# LB_o9_Bargraph-v03_3_3.net
KiCad netlist of a schematic drawn in EAGLE
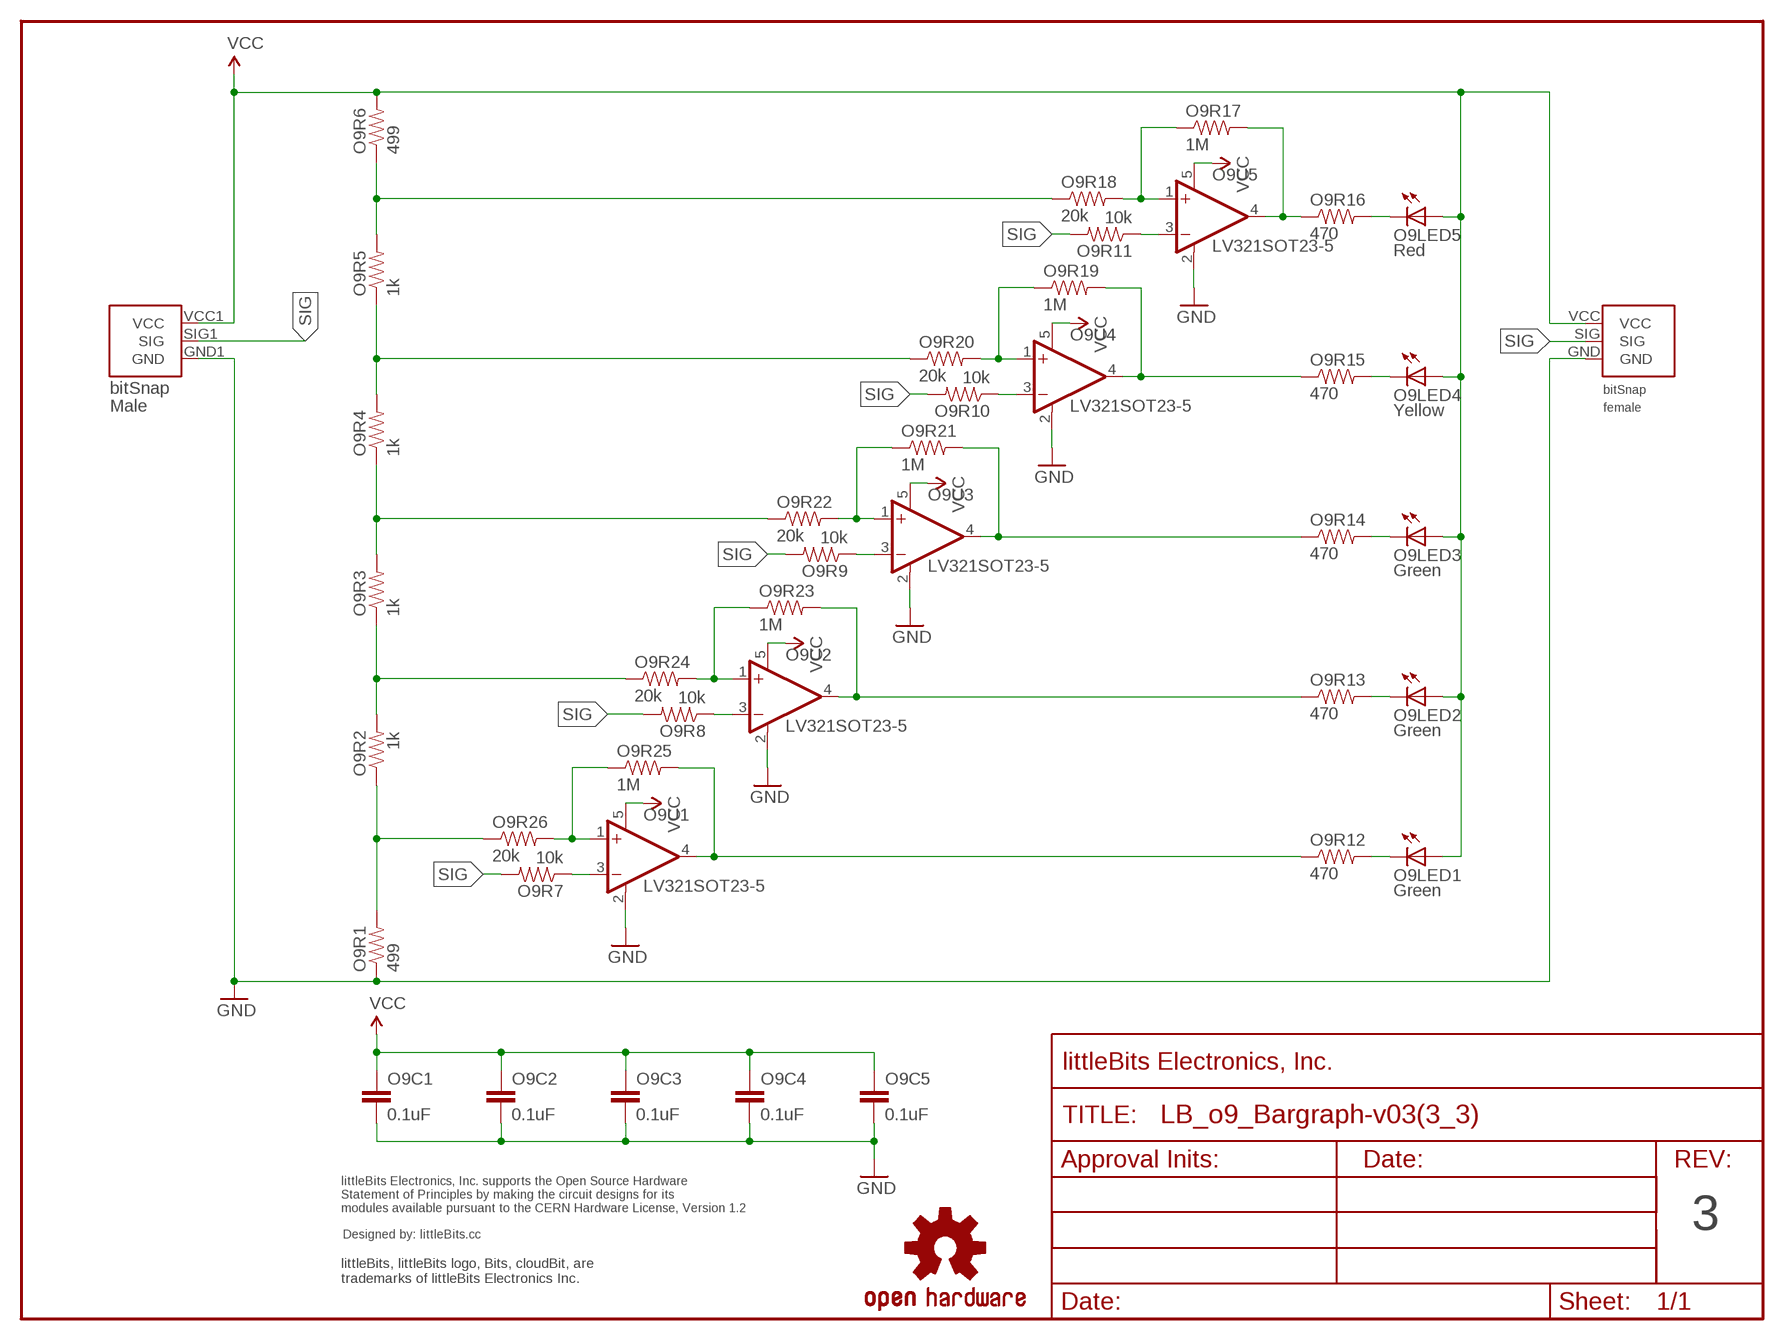
[diagram p0: schematic, sheet 1]

(export (version "E")
  (design (tool "Eeschema 10.0.6"))
  (components
    (comp (ref "09BSF1")
      (value "BITSNAP_V03_FEMALE")
      (footprint "eagle-import:BITSNAP_V03_FEMALE")
      (libsource (lib "eagle-import") (part "BITSNAP_V03_FEMALE"))
    )
    (comp (ref "O9BSM1")
      (value "BITSNAP_V03_MALE")
      (footprint "eagle-import:BITSNAP_V03_MALE")
      (libsource (lib "eagle-import") (part "BITSNAP_V03_MALE"))
    )
    (comp (ref "O9C1")
      (value "0.1uF")
      (footprint "eagle-import:0603-CAP")
      (libsource (lib "eagle-import") (part "CAP0603-CAP"))
    )
    (comp (ref "O9C2")
      (value "0.1uF")
      (footprint "eagle-import:0603-CAP")
      (libsource (lib "eagle-import") (part "CAP0603-CAP"))
    )
    (comp (ref "O9C3")
      (value "0.1uF")
      (footprint "eagle-import:0603-CAP")
      (libsource (lib "eagle-import") (part "CAP0603-CAP"))
    )
    (comp (ref "O9C4")
      (value "0.1uF")
      (footprint "eagle-import:0603-CAP")
      (libsource (lib "eagle-import") (part "CAP0603-CAP"))
    )
    (comp (ref "O9C5")
      (value "0.1uF")
      (footprint "eagle-import:0603-CAP")
      (libsource (lib "eagle-import") (part "CAP0603-CAP"))
    )
    (comp (ref "O9LED1")
      (value "Green")
      (footprint "eagle-import:LED-1206")
      (libsource (lib "eagle-import") (part "LED1206"))
    )
    (comp (ref "O9LED2")
      (value "Green")
      (footprint "eagle-import:LED-1206")
      (libsource (lib "eagle-import") (part "LED1206"))
    )
    (comp (ref "O9LED3")
      (value "Green")
      (footprint "eagle-import:LED-1206")
      (libsource (lib "eagle-import") (part "LED1206"))
    )
    (comp (ref "O9LED4")
      (value "Yellow")
      (footprint "eagle-import:LED-1206")
      (libsource (lib "eagle-import") (part "LED1206"))
    )
    (comp (ref "O9LED5")
      (value "Red")
      (footprint "eagle-import:LED-1206")
      (libsource (lib "eagle-import") (part "LED1206"))
    )
    (comp (ref "O9R1")
      (value "499")
      (footprint "eagle-import:0603-RES")
      (libsource (lib "eagle-import") (part "RESISTOR0603-RES"))
    )
    (comp (ref "O9R2")
      (value "1k")
      (footprint "eagle-import:0603-RES")
      (libsource (lib "eagle-import") (part "RESISTOR0603-RES"))
    )
    (comp (ref "O9R3")
      (value "1k")
      (footprint "eagle-import:0603-RES")
      (libsource (lib "eagle-import") (part "RESISTOR0603-RES"))
    )
    (comp (ref "O9R4")
      (value "1k")
      (footprint "eagle-import:0603-RES")
      (libsource (lib "eagle-import") (part "RESISTOR0603-RES"))
    )
    (comp (ref "O9R5")
      (value "1k")
      (footprint "eagle-import:0603-RES")
      (libsource (lib "eagle-import") (part "RESISTOR0603-RES"))
    )
    (comp (ref "O9R6")
      (value "499")
      (footprint "eagle-import:0603-RES")
      (libsource (lib "eagle-import") (part "RESISTOR0603-RES"))
    )
    (comp (ref "O9R7")
      (value "10k")
      (footprint "eagle-import:0603-RES")
      (libsource (lib "eagle-import") (part "RESISTOR0603-RES"))
    )
    (comp (ref "O9R8")
      (value "10k")
      (footprint "eagle-import:0603-RES")
      (libsource (lib "eagle-import") (part "RESISTOR0603-RES"))
    )
    (comp (ref "O9R9")
      (value "10k")
      (footprint "eagle-import:0603-RES")
      (libsource (lib "eagle-import") (part "RESISTOR0603-RES"))
    )
    (comp (ref "O9R10")
      (value "10k")
      (footprint "eagle-import:0603-RES")
      (libsource (lib "eagle-import") (part "RESISTOR0603-RES"))
    )
    (comp (ref "O9R11")
      (value "10k")
      (footprint "eagle-import:0603-RES")
      (libsource (lib "eagle-import") (part "RESISTOR0603-RES"))
    )
    (comp (ref "O9R12")
      (value "470")
      (footprint "eagle-import:0603-RES")
      (libsource (lib "eagle-import") (part "RESISTOR0603-RES"))
    )
    (comp (ref "O9R13")
      (value "470")
      (footprint "eagle-import:0603-RES")
      (libsource (lib "eagle-import") (part "RESISTOR0603-RES"))
    )
    (comp (ref "O9R14")
      (value "470")
      (footprint "eagle-import:0603-RES")
      (libsource (lib "eagle-import") (part "RESISTOR0603-RES"))
    )
    (comp (ref "O9R15")
      (value "470")
      (footprint "eagle-import:0603-RES")
      (libsource (lib "eagle-import") (part "RESISTOR0603-RES"))
    )
    (comp (ref "O9R16")
      (value "470")
      (footprint "eagle-import:0603-RES")
      (libsource (lib "eagle-import") (part "RESISTOR0603-RES"))
    )
    (comp (ref "O9R17")
      (value "1M")
      (footprint "eagle-import:0603-RES")
      (libsource (lib "eagle-import") (part "RESISTOR0603-RES"))
    )
    (comp (ref "O9R18")
      (value "20k")
      (footprint "eagle-import:0603-RES")
      (libsource (lib "eagle-import") (part "RESISTOR0603-RES"))
    )
    (comp (ref "O9R19")
      (value "1M")
      (footprint "eagle-import:0603-RES")
      (libsource (lib "eagle-import") (part "RESISTOR0603-RES"))
    )
    (comp (ref "O9R20")
      (value "20k")
      (footprint "eagle-import:0603-RES")
      (libsource (lib "eagle-import") (part "RESISTOR0603-RES"))
    )
    (comp (ref "O9R21")
      (value "1M")
      (footprint "eagle-import:0603-RES")
      (libsource (lib "eagle-import") (part "RESISTOR0603-RES"))
    )
    (comp (ref "O9R22")
      (value "20k")
      (footprint "eagle-import:0603-RES")
      (libsource (lib "eagle-import") (part "RESISTOR0603-RES"))
    )
    (comp (ref "O9R23")
      (value "1M")
      (footprint "eagle-import:0603-RES")
      (libsource (lib "eagle-import") (part "RESISTOR0603-RES"))
    )
    (comp (ref "O9R24")
      (value "20k")
      (footprint "eagle-import:0603-RES")
      (libsource (lib "eagle-import") (part "RESISTOR0603-RES"))
    )
    (comp (ref "O9R25")
      (value "1M")
      (footprint "eagle-import:0603-RES")
      (libsource (lib "eagle-import") (part "RESISTOR0603-RES"))
    )
    (comp (ref "O9R26")
      (value "20k")
      (footprint "eagle-import:0603-RES")
      (libsource (lib "eagle-import") (part "RESISTOR0603-RES"))
    )
    (comp (ref "O9U1")
      (value "LV321SOT23-5")
      (footprint "eagle-import:SOT23-5")
      (libsource (lib "eagle-import") (part "LV321SOT23-5"))
    )
    (comp (ref "O9U2")
      (value "LV321SOT23-5")
      (footprint "eagle-import:SOT23-5")
      (libsource (lib "eagle-import") (part "LV321SOT23-5"))
    )
    (comp (ref "O9U3")
      (value "LV321SOT23-5")
      (footprint "eagle-import:SOT23-5")
      (libsource (lib "eagle-import") (part "LV321SOT23-5"))
    )
    (comp (ref "O9U4")
      (value "LV321SOT23-5")
      (footprint "eagle-import:SOT23-5")
      (libsource (lib "eagle-import") (part "LV321SOT23-5"))
    )
    (comp (ref "O9U5")
      (value "LV321SOT23-5")
      (footprint "eagle-import:SOT23-5")
      (libsource (lib "eagle-import") (part "LV321SOT23-5"))
    )
    (comp (ref "U$1")
      (value "OSHWCREDIT")
      (footprint "eagle-import:OSHWCREDIT")
      (libsource (lib "eagle-import") (part "OSHWCREDIT"))
    )
    (comp (ref "U$2")
      (value "FRAME-LETTER-OHWOHW")
      (footprint "eagle-import:FABDWG01-OHW")
      (libsource (lib "eagle-import") (part "FRAME-LETTER-OHWOHW"))
    )
    (comp (ref "U$4")
      (value "OSHW-LOGOL")
      (footprint "eagle-import:OSHW-LOGO-L")
      (libsource (lib "eagle-import") (part "OSHW-LOGOL"))
    )
  )
  (nets
    (net (code "1") (name "GND") (class "Default")
      (node (ref "09BSF1") (pin "GND") (pinfunction "GND_GND") (pintype "bidirectional"))
      (node (ref "O9BSM1") (pin "GND1") (pinfunction "GND_GND1") (pintype "bidirectional"))
      (node (ref "O9C1") (pin "2") (pinfunction "2_2") (pintype "passive"))
      (node (ref "O9C2") (pin "2") (pinfunction "2_2") (pintype "passive"))
      (node (ref "O9C3") (pin "2") (pinfunction "2_2") (pintype "passive"))
      (node (ref "O9C4") (pin "2") (pinfunction "2_2") (pintype "passive"))
      (node (ref "O9C5") (pin "2") (pinfunction "2_2") (pintype "passive"))
      (node (ref "O9R1") (pin "1") (pinfunction "1_1") (pintype "passive"))
      (node (ref "O9U1") (pin "2") (pinfunction "V-_2") (pintype "power_in"))
      (node (ref "O9U2") (pin "2") (pinfunction "V-_2") (pintype "power_in"))
      (node (ref "O9U3") (pin "2") (pinfunction "V-_2") (pintype "power_in"))
      (node (ref "O9U4") (pin "2") (pinfunction "V-_2") (pintype "power_in"))
      (node (ref "O9U5") (pin "2") (pinfunction "V-_2") (pintype "power_in"))
    )
    (net (code "2") (name "Net-(O9LED1-PadC)") (class "Default")
      (node (ref "O9LED1") (pin "C") (pinfunction "C_C") (pintype "passive"))
      (node (ref "O9R12") (pin "2") (pinfunction "2_2") (pintype "passive"))
    )
    (net (code "3") (name "Net-(O9LED2-PadC)") (class "Default")
      (node (ref "O9LED2") (pin "C") (pinfunction "C_C") (pintype "passive"))
      (node (ref "O9R13") (pin "2") (pinfunction "2_2") (pintype "passive"))
    )
    (net (code "4") (name "Net-(O9LED3-PadC)") (class "Default")
      (node (ref "O9LED3") (pin "C") (pinfunction "C_C") (pintype "passive"))
      (node (ref "O9R14") (pin "2") (pinfunction "2_2") (pintype "passive"))
    )
    (net (code "5") (name "Net-(O9LED4-PadC)") (class "Default")
      (node (ref "O9LED4") (pin "C") (pinfunction "C_C") (pintype "passive"))
      (node (ref "O9R15") (pin "2") (pinfunction "2_2") (pintype "passive"))
    )
    (net (code "6") (name "Net-(O9LED5-PadC)") (class "Default")
      (node (ref "O9LED5") (pin "C") (pinfunction "C_C") (pintype "passive"))
      (node (ref "O9R16") (pin "2") (pinfunction "2_2") (pintype "passive"))
    )
    (net (code "7") (name "Net-(O9R1-Pad2)") (class "Default")
      (node (ref "O9R1") (pin "2") (pinfunction "2_2") (pintype "passive"))
      (node (ref "O9R2") (pin "1") (pinfunction "1_1") (pintype "passive"))
      (node (ref "O9R26") (pin "1") (pinfunction "1_1") (pintype "passive"))
    )
    (net (code "8") (name "Net-(O9R2-Pad2)") (class "Default")
      (node (ref "O9R2") (pin "2") (pinfunction "2_2") (pintype "passive"))
      (node (ref "O9R24") (pin "1") (pinfunction "1_1") (pintype "passive"))
      (node (ref "O9R3") (pin "1") (pinfunction "1_1") (pintype "passive"))
    )
    (net (code "9") (name "Net-(O9R18-Pad1)") (class "Default")
      (node (ref "O9R18") (pin "1") (pinfunction "1_1") (pintype "passive"))
      (node (ref "O9R5") (pin "2") (pinfunction "2_2") (pintype "passive"))
      (node (ref "O9R6") (pin "1") (pinfunction "1_1") (pintype "passive"))
    )
    (net (code "10") (name "Net-(O9R20-Pad1)") (class "Default")
      (node (ref "O9R20") (pin "1") (pinfunction "1_1") (pintype "passive"))
      (node (ref "O9R4") (pin "2") (pinfunction "2_2") (pintype "passive"))
      (node (ref "O9R5") (pin "1") (pinfunction "1_1") (pintype "passive"))
    )
    (net (code "11") (name "Net-(O9R22-Pad1)") (class "Default")
      (node (ref "O9R22") (pin "1") (pinfunction "1_1") (pintype "passive"))
      (node (ref "O9R3") (pin "2") (pinfunction "2_2") (pintype "passive"))
      (node (ref "O9R4") (pin "1") (pinfunction "1_1") (pintype "passive"))
    )
    (net (code "12") (name "Net-(O9U1-+IN)") (class "Default")
      (node (ref "O9R25") (pin "1") (pinfunction "1_1") (pintype "passive"))
      (node (ref "O9R26") (pin "2") (pinfunction "2_2") (pintype "passive"))
      (node (ref "O9U1") (pin "1") (pinfunction "+IN_1") (pintype "input"))
    )
    (net (code "13") (name "Net-(O9U1--IN)") (class "Default")
      (node (ref "O9R7") (pin "1") (pinfunction "1_1") (pintype "passive"))
      (node (ref "O9U1") (pin "3") (pinfunction "-IN_3") (pintype "input"))
    )
    (net (code "14") (name "Net-(O9U1-OUT)") (class "Default")
      (node (ref "O9R12") (pin "1") (pinfunction "1_1") (pintype "passive"))
      (node (ref "O9R25") (pin "2") (pinfunction "2_2") (pintype "passive"))
      (node (ref "O9U1") (pin "4") (pinfunction "OUT_4") (pintype "output"))
    )
    (net (code "15") (name "Net-(O9U2-+IN)") (class "Default")
      (node (ref "O9R23") (pin "1") (pinfunction "1_1") (pintype "passive"))
      (node (ref "O9R24") (pin "2") (pinfunction "2_2") (pintype "passive"))
      (node (ref "O9U2") (pin "1") (pinfunction "+IN_1") (pintype "input"))
    )
    (net (code "16") (name "Net-(O9U2--IN)") (class "Default")
      (node (ref "O9R8") (pin "1") (pinfunction "1_1") (pintype "passive"))
      (node (ref "O9U2") (pin "3") (pinfunction "-IN_3") (pintype "input"))
    )
    (net (code "17") (name "Net-(O9U2-OUT)") (class "Default")
      (node (ref "O9R13") (pin "1") (pinfunction "1_1") (pintype "passive"))
      (node (ref "O9R23") (pin "2") (pinfunction "2_2") (pintype "passive"))
      (node (ref "O9U2") (pin "4") (pinfunction "OUT_4") (pintype "output"))
    )
    (net (code "18") (name "Net-(O9U3-+IN)") (class "Default")
      (node (ref "O9R21") (pin "1") (pinfunction "1_1") (pintype "passive"))
      (node (ref "O9R22") (pin "2") (pinfunction "2_2") (pintype "passive"))
      (node (ref "O9U3") (pin "1") (pinfunction "+IN_1") (pintype "input"))
    )
    (net (code "19") (name "Net-(O9U3--IN)") (class "Default")
      (node (ref "O9R9") (pin "1") (pinfunction "1_1") (pintype "passive"))
      (node (ref "O9U3") (pin "3") (pinfunction "-IN_3") (pintype "input"))
    )
    (net (code "20") (name "Net-(O9U3-OUT)") (class "Default")
      (node (ref "O9R14") (pin "1") (pinfunction "1_1") (pintype "passive"))
      (node (ref "O9R21") (pin "2") (pinfunction "2_2") (pintype "passive"))
      (node (ref "O9U3") (pin "4") (pinfunction "OUT_4") (pintype "output"))
    )
    (net (code "21") (name "Net-(O9U4-+IN)") (class "Default")
      (node (ref "O9R19") (pin "1") (pinfunction "1_1") (pintype "passive"))
      (node (ref "O9R20") (pin "2") (pinfunction "2_2") (pintype "passive"))
      (node (ref "O9U4") (pin "1") (pinfunction "+IN_1") (pintype "input"))
    )
    (net (code "22") (name "Net-(O9U4--IN)") (class "Default")
      (node (ref "O9R10") (pin "1") (pinfunction "1_1") (pintype "passive"))
      (node (ref "O9U4") (pin "3") (pinfunction "-IN_3") (pintype "input"))
    )
    (net (code "23") (name "Net-(O9U4-OUT)") (class "Default")
      (node (ref "O9R15") (pin "1") (pinfunction "1_1") (pintype "passive"))
      (node (ref "O9R19") (pin "2") (pinfunction "2_2") (pintype "passive"))
      (node (ref "O9U4") (pin "4") (pinfunction "OUT_4") (pintype "output"))
    )
    (net (code "24") (name "Net-(O9U5-+IN)") (class "Default")
      (node (ref "O9R17") (pin "1") (pinfunction "1_1") (pintype "passive"))
      (node (ref "O9R18") (pin "2") (pinfunction "2_2") (pintype "passive"))
      (node (ref "O9U5") (pin "1") (pinfunction "+IN_1") (pintype "input"))
    )
    (net (code "25") (name "Net-(O9U5--IN)") (class "Default")
      (node (ref "O9R11") (pin "1") (pinfunction "1_1") (pintype "passive"))
      (node (ref "O9U5") (pin "3") (pinfunction "-IN_3") (pintype "input"))
    )
    (net (code "26") (name "Net-(O9U5-OUT)") (class "Default")
      (node (ref "O9R16") (pin "1") (pinfunction "1_1") (pintype "passive"))
      (node (ref "O9R17") (pin "2") (pinfunction "2_2") (pintype "passive"))
      (node (ref "O9U5") (pin "4") (pinfunction "OUT_4") (pintype "output"))
    )
    (net (code "27") (name "SIG") (class "Default")
      (node (ref "09BSF1") (pin "SIG") (pinfunction "SIG_SIG") (pintype "bidirectional"))
      (node (ref "O9BSM1") (pin "SIG1") (pinfunction "SIG_SIG1") (pintype "bidirectional"))
      (node (ref "O9R10") (pin "2") (pinfunction "2_2") (pintype "passive"))
      (node (ref "O9R11") (pin "2") (pinfunction "2_2") (pintype "passive"))
      (node (ref "O9R7") (pin "2") (pinfunction "2_2") (pintype "passive"))
      (node (ref "O9R8") (pin "2") (pinfunction "2_2") (pintype "passive"))
      (node (ref "O9R9") (pin "2") (pinfunction "2_2") (pintype "passive"))
    )
    (net (code "28") (name "VCC") (class "Default")
      (node (ref "09BSF1") (pin "VCC") (pinfunction "VCC_VCC") (pintype "bidirectional"))
      (node (ref "O9BSM1") (pin "VCC1") (pinfunction "VCC_VCC1") (pintype "bidirectional"))
      (node (ref "O9C1") (pin "1") (pinfunction "1_1") (pintype "passive"))
      (node (ref "O9C2") (pin "1") (pinfunction "1_1") (pintype "passive"))
      (node (ref "O9C3") (pin "1") (pinfunction "1_1") (pintype "passive"))
      (node (ref "O9C4") (pin "1") (pinfunction "1_1") (pintype "passive"))
      (node (ref "O9C5") (pin "1") (pinfunction "1_1") (pintype "passive"))
      (node (ref "O9LED1") (pin "A") (pinfunction "A_A") (pintype "passive"))
      (node (ref "O9LED2") (pin "A") (pinfunction "A_A") (pintype "passive"))
      (node (ref "O9LED3") (pin "A") (pinfunction "A_A") (pintype "passive"))
      (node (ref "O9LED4") (pin "A") (pinfunction "A_A") (pintype "passive"))
      (node (ref "O9LED5") (pin "A") (pinfunction "A_A") (pintype "passive"))
      (node (ref "O9R6") (pin "2") (pinfunction "2_2") (pintype "passive"))
      (node (ref "O9U1") (pin "5") (pinfunction "V+_5") (pintype "power_in"))
      (node (ref "O9U2") (pin "5") (pinfunction "V+_5") (pintype "power_in"))
      (node (ref "O9U3") (pin "5") (pinfunction "V+_5") (pintype "power_in"))
      (node (ref "O9U4") (pin "5") (pinfunction "V+_5") (pintype "power_in"))
      (node (ref "O9U5") (pin "5") (pinfunction "V+_5") (pintype "power_in"))
    )
  )
)
